# DasAltimeter_V0_3.net
KiCad netlist of a schematic drawn in EAGLE
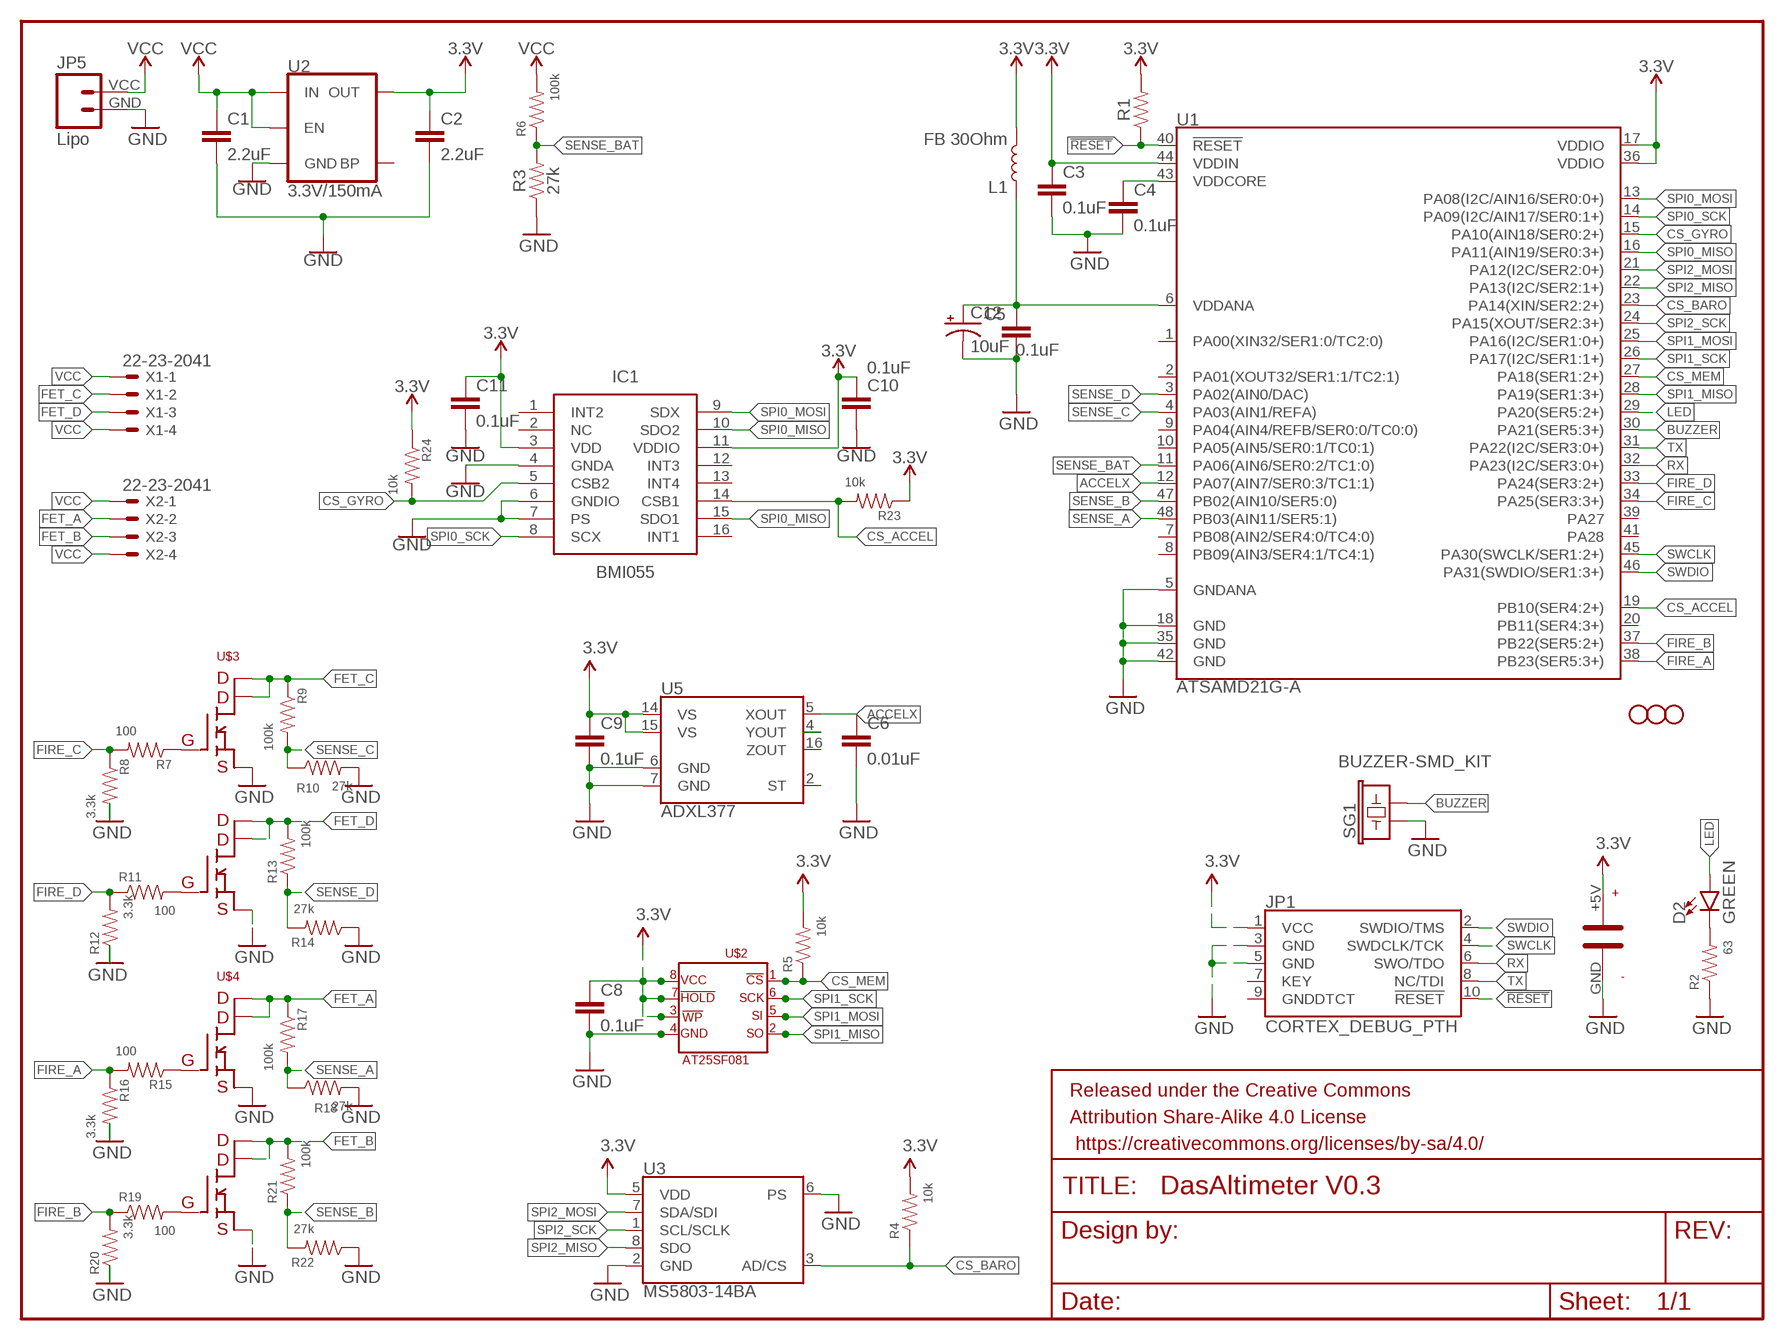
[diagram p0: schematic, sheet 1]

(export (version "E")
  (design (tool "Eeschema 10.0.6"))
  (components
    (comp (ref "C1")
      (value "2.2uF")
      (footprint "eagle-import:0603")
      (libsource (lib "eagle-import") (part "2.2UF-0603-10V-20%"))
    )
    (comp (ref "C2")
      (value "2.2uF")
      (footprint "eagle-import:0603")
      (libsource (lib "eagle-import") (part "2.2UF-0603-10V-20%"))
    )
    (comp (ref "C3")
      (value "0.1uF")
      (footprint "eagle-import:0402")
      (libsource (lib "eagle-import") (part "0.1UF-0402-16V-10%"))
    )
    (comp (ref "C4")
      (value "0.1uF")
      (footprint "eagle-import:0402")
      (libsource (lib "eagle-import") (part "0.1UF-0402-16V-10%"))
    )
    (comp (ref "C5")
      (value "0.1uF")
      (footprint "eagle-import:0402")
      (libsource (lib "eagle-import") (part "0.1UF-0402-16V-10%"))
    )
    (comp (ref "C6")
      (value "0.01uF")
      (footprint "eagle-import:0402")
      (libsource (lib "eagle-import") (part "0.1UF-0402-16V-10%"))
    )
    (comp (ref "C8")
      (value "0.1uF")
      (footprint "eagle-import:0402")
      (libsource (lib "eagle-import") (part "0.1UF-0402-16V-10%"))
    )
    (comp (ref "C9")
      (value "0.1uF")
      (footprint "eagle-import:0402")
      (libsource (lib "eagle-import") (part "0.1UF-0402-16V-10%"))
    )
    (comp (ref "C10")
      (value "0.1uF")
      (footprint "eagle-import:0402")
      (libsource (lib "eagle-import") (part "0.1UF-0402-16V-10%"))
    )
    (comp (ref "C11")
      (value "0.1uF")
      (footprint "eagle-import:0402")
      (libsource (lib "eagle-import") (part "0.1UF-0402-16V-10%"))
    )
    (comp (ref "C12")
      (value "10uF")
      (footprint "eagle-import:0603-POLAR")
      (libsource (lib "eagle-import") (part "10UF-POLAR-0603-6.3V-20%(TANT)"))
    )
    (comp (ref "D2")
      (value "GREEN")
      (footprint "eagle-import:LED-1206")
      (libsource (lib "eagle-import") (part "LED-GREEN1206"))
    )
    (comp (ref "FRAME1")
      (value "FRAME-LETTERNO_PACKAGE")
      (footprint "eagle-import:DUMMY")
      (fields (field (name "DESIGNER") "Nobody"))
      (libsource (lib "eagle-import") (part "FRAME-LETTERNO_PACKAGE"))
    )
    (comp (ref "H1")
      (value "STAND-OFFTIGHT")
      (footprint "eagle-import:STAND-OFF-TIGHT")
      (libsource (lib "eagle-import") (part "STAND-OFFTIGHT"))
    )
    (comp (ref "H2")
      (value "STAND-OFFTIGHT")
      (footprint "eagle-import:STAND-OFF-TIGHT")
      (libsource (lib "eagle-import") (part "STAND-OFFTIGHT"))
    )
    (comp (ref "H3")
      (value "STAND-OFFTIGHT")
      (footprint "eagle-import:STAND-OFF-TIGHT")
      (libsource (lib "eagle-import") (part "STAND-OFFTIGHT"))
    )
    (comp (ref "IC1")
      (value "BMI055")
      (footprint "eagle-import:BMI055")
      (libsource (lib "eagle-import") (part "BMI055"))
    )
    (comp (ref "JP1")
      (value "CORTEX_DEBUG_PTH")
      (footprint "eagle-import:2X5-PTH-1.27MM")
      (libsource (lib "eagle-import") (part "CORTEX_DEBUG_PTH"))
    )
    (comp (ref "JP5")
      (value "Lipo")
      (footprint "eagle-import:JST-2-SMD-VERT")
      (libsource (lib "eagle-import") (part "M024UCON-15767"))
    )
    (comp (ref "L1")
      (value "FB 30Ohm")
      (footprint "eagle-import:0603")
      (libsource (lib "eagle-import") (part "INDUCTOR-0603-33NH"))
    )
    (comp (ref "R1")
      (value "RESISTOR0402")
      (footprint "eagle-import:0402")
      (libsource (lib "eagle-import") (part "RESISTOR0402"))
    )
    (comp (ref "R2")
      (value "63")
      (footprint "eagle-import:0402")
      (libsource (lib "eagle-import") (part "RESISTOR0402"))
    )
    (comp (ref "R3")
      (value "27k")
      (footprint "eagle-import:0402")
      (libsource (lib "eagle-import") (part "RESISTOR0402"))
    )
    (comp (ref "R4")
      (value "10k")
      (footprint "eagle-import:0402")
      (libsource (lib "eagle-import") (part "RESISTOR0402"))
    )
    (comp (ref "R5")
      (value "10k")
      (footprint "eagle-import:0402")
      (libsource (lib "eagle-import") (part "RESISTOR0402"))
    )
    (comp (ref "R6")
      (value "100k")
      (footprint "eagle-import:0402")
      (libsource (lib "eagle-import") (part "RESISTOR0402"))
    )
    (comp (ref "R7")
      (value "100")
      (footprint "eagle-import:0402")
      (libsource (lib "eagle-import") (part "RESISTOR0402"))
    )
    (comp (ref "R8")
      (value "3.3k")
      (footprint "eagle-import:0402")
      (libsource (lib "eagle-import") (part "RESISTOR0402"))
    )
    (comp (ref "R9")
      (value "100k")
      (footprint "eagle-import:0402")
      (libsource (lib "eagle-import") (part "RESISTOR0402"))
    )
    (comp (ref "R10")
      (value "27k")
      (footprint "eagle-import:0402")
      (libsource (lib "eagle-import") (part "RESISTOR0402"))
    )
    (comp (ref "R11")
      (value "100")
      (footprint "eagle-import:0402")
      (libsource (lib "eagle-import") (part "RESISTOR0402"))
    )
    (comp (ref "R12")
      (value "3.3k")
      (footprint "eagle-import:0402")
      (libsource (lib "eagle-import") (part "RESISTOR0402"))
    )
    (comp (ref "R13")
      (value "100k")
      (footprint "eagle-import:0402")
      (libsource (lib "eagle-import") (part "RESISTOR0402"))
    )
    (comp (ref "R14")
      (value "27k")
      (footprint "eagle-import:0402")
      (libsource (lib "eagle-import") (part "RESISTOR0402"))
    )
    (comp (ref "R15")
      (value "100")
      (footprint "eagle-import:0402")
      (libsource (lib "eagle-import") (part "RESISTOR0402"))
    )
    (comp (ref "R16")
      (value "3.3k")
      (footprint "eagle-import:0402")
      (libsource (lib "eagle-import") (part "RESISTOR0402"))
    )
    (comp (ref "R17")
      (value "100k")
      (footprint "eagle-import:0402")
      (libsource (lib "eagle-import") (part "RESISTOR0402"))
    )
    (comp (ref "R18")
      (value "27k")
      (footprint "eagle-import:0402")
      (libsource (lib "eagle-import") (part "RESISTOR0402"))
    )
    (comp (ref "R19")
      (value "100")
      (footprint "eagle-import:0402")
      (libsource (lib "eagle-import") (part "RESISTOR0402"))
    )
    (comp (ref "R20")
      (value "3.3k")
      (footprint "eagle-import:0402")
      (libsource (lib "eagle-import") (part "RESISTOR0402"))
    )
    (comp (ref "R21")
      (value "100k")
      (footprint "eagle-import:0402")
      (libsource (lib "eagle-import") (part "RESISTOR0402"))
    )
    (comp (ref "R22")
      (value "27k")
      (footprint "eagle-import:0402")
      (libsource (lib "eagle-import") (part "RESISTOR0402"))
    )
    (comp (ref "R23")
      (value "10k")
      (footprint "eagle-import:0402")
      (libsource (lib "eagle-import") (part "RESISTOR0402"))
    )
    (comp (ref "R24")
      (value "10k")
      (footprint "eagle-import:0402")
      (libsource (lib "eagle-import") (part "RESISTOR0402"))
    )
    (comp (ref "SG1")
      (value "BUZZER-SMD_KIT")
      (footprint "eagle-import:BUZZER-CCV-KIT")
      (libsource (lib "eagle-import") (part "BUZZER-SMD_KIT"))
    )
    (comp (ref "U$1")
      (value "PB-5R0H104-R")
      (footprint "eagle-import:PB-5R0H104-R")
      (libsource (lib "eagle-import") (part "PB-5R0H104-R"))
    )
    (comp (ref "U$2")
      (value "AT25SF081")
      (footprint "eagle-import:AT25SF081")
      (libsource (lib "eagle-import") (part "AT25SF081"))
    )
    (comp (ref "U$3")
      (value "SI7232DN")
      (footprint "eagle-import:SI7232DN")
      (libsource (lib "eagle-import") (part "SI7232DN"))
    )
    (comp (ref "U$4")
      (value "SI7232DN")
      (footprint "eagle-import:SI7232DN")
      (libsource (lib "eagle-import") (part "SI7232DN"))
    )
    (comp (ref "U1")
      (value "ATSAMD21G-A")
      (footprint "eagle-import:TQFP-48")
      (libsource (lib "eagle-import") (part "ATSAMD21G-A"))
    )
    (comp (ref "U2")
      (value "3.3V/150mA")
      (footprint "eagle-import:SOT23-5")
      (libsource (lib "eagle-import") (part "V_REG_MIC52053.3V"))
    )
    (comp (ref "U3")
      (value "MS5803-14BA")
      (footprint "eagle-import:MS5803")
      (libsource (lib "eagle-import") (part "MS5803-14BA"))
    )
    (comp (ref "U5")
      (value "ADXL377")
      (footprint "eagle-import:LFCSP-16-3X3")
      (libsource (lib "eagle-import") (part "ADXL377"))
    )
    (comp (ref "X1")
      (value "22-23-2041")
      (footprint "eagle-import:22-23-2041")
      (fields (field (name "MF") "MOLEX"))
      (libsource (lib "eagle-import") (part "22-23-2041"))
    )
    (comp (ref "X2")
      (value "22-23-2041")
      (footprint "eagle-import:22-23-2041")
      (fields (field (name "MF") "MOLEX"))
      (libsource (lib "eagle-import") (part "22-23-2041"))
    )
  )
  (nets
    (net (code "1") (name "/~{RESET}") (class "Default")
      (node (ref "JP1") (pin "10") (pinfunction "~{RESET}_10") (pintype "bidirectional"))
      (node (ref "R1") (pin "1") (pinfunction "1_1") (pintype "passive"))
      (node (ref "U1") (pin "40") (pinfunction "~{RESET}_40") (pintype "bidirectional"))
    )
    (net (code "2") (name "3.3V") (class "Default")
      (node (ref "C10") (pin "1") (pinfunction "1_1") (pintype "passive"))
      (node (ref "C11") (pin "1") (pinfunction "1_1") (pintype "passive"))
      (node (ref "C2") (pin "1") (pinfunction "1_1") (pintype "passive"))
      (node (ref "C3") (pin "1") (pinfunction "1_1") (pintype "passive"))
      (node (ref "C8") (pin "1") (pinfunction "1_1") (pintype "passive"))
      (node (ref "C9") (pin "1") (pinfunction "1_1") (pintype "passive"))
      (node (ref "IC1") (pin "11") (pinfunction "VDDIO_11") (pintype "passive"))
      (node (ref "IC1") (pin "3") (pinfunction "VDD_3") (pintype "passive"))
      (node (ref "JP1") (pin "1") (pinfunction "VCC_1") (pintype "bidirectional"))
      (node (ref "L1") (pin "2") (pinfunction "2_2") (pintype "passive"))
      (node (ref "R1") (pin "2") (pinfunction "2_2") (pintype "passive"))
      (node (ref "R23") (pin "1") (pinfunction "1_1") (pintype "passive"))
      (node (ref "R24") (pin "1") (pinfunction "1_1") (pintype "passive"))
      (node (ref "R4") (pin "2") (pinfunction "2_2") (pintype "passive"))
      (node (ref "R5") (pin "2") (pinfunction "2_2") (pintype "passive"))
      (node (ref "U$1") (pin "+5V") (pinfunction "+5V_+5V") (pintype "bidirectional"))
      (node (ref "U$2") (pin "!HOLD") (pinfunction "~{HOLD}_!HOLD") (pintype "bidirectional"))
      (node (ref "U$2") (pin "!WP") (pinfunction "~{WP}_!WP") (pintype "bidirectional"))
      (node (ref "U$2") (pin "VCC") (pinfunction "VCC_VCC") (pintype "bidirectional"))
      (node (ref "U1") (pin "17") (pinfunction "VDDIO_17") (pintype "bidirectional"))
      (node (ref "U1") (pin "36") (pinfunction "VDDIO_36") (pintype "bidirectional"))
      (node (ref "U1") (pin "44") (pinfunction "VDDIN_44") (pintype "bidirectional"))
      (node (ref "U2") (pin "5") (pinfunction "OUT_5") (pintype "passive"))
      (node (ref "U3") (pin "5") (pinfunction "VDD_5") (pintype "bidirectional"))
      (node (ref "U5") (pin "14") (pinfunction "VS_14") (pintype "bidirectional"))
      (node (ref "U5") (pin "15") (pinfunction "VS_15") (pintype "bidirectional"))
    )
    (net (code "3") (name "ACCELX") (class "Default")
      (node (ref "C6") (pin "1") (pinfunction "1_1") (pintype "passive"))
      (node (ref "U1") (pin "12") (pinfunction "PA07(AIN7/SER0:3/TC1:1)_12") (pintype "bidirectional"))
      (node (ref "U5") (pin "5") (pinfunction "XOUT_5") (pintype "bidirectional"))
    )
    (net (code "4") (name "BUZZER") (class "Default")
      (node (ref "SG1") (pin "-") (pinfunction "2_-") (pintype "passive"))
      (node (ref "U1") (pin "30") (pinfunction "PA21(SER5:3+)_30") (pintype "bidirectional"))
    )
    (net (code "5") (name "CS_ACCEL") (class "Default")
      (node (ref "IC1") (pin "14") (pinfunction "CSB1_14") (pintype "passive"))
      (node (ref "R23") (pin "2") (pinfunction "2_2") (pintype "passive"))
      (node (ref "U1") (pin "19") (pinfunction "PB10(SER4:2+)_19") (pintype "bidirectional"))
    )
    (net (code "6") (name "CS_BARO") (class "Default")
      (node (ref "R4") (pin "1") (pinfunction "1_1") (pintype "passive"))
      (node (ref "U1") (pin "23") (pinfunction "PA14(XIN/SER2:2+)_23") (pintype "bidirectional"))
      (node (ref "U3") (pin "3") (pinfunction "AD/CS_3") (pintype "bidirectional"))
    )
    (net (code "7") (name "CS_GYRO") (class "Default")
      (node (ref "IC1") (pin "5") (pinfunction "CSB2_5") (pintype "passive"))
      (node (ref "R24") (pin "2") (pinfunction "2_2") (pintype "passive"))
      (node (ref "U1") (pin "15") (pinfunction "PA10(AIN18/SER0:2+)_15") (pintype "bidirectional"))
    )
    (net (code "8") (name "CS_MEM") (class "Default")
      (node (ref "R5") (pin "1") (pinfunction "1_1") (pintype "passive"))
      (node (ref "U$2") (pin "!CS") (pinfunction "~{CS}_!CS") (pintype "bidirectional"))
      (node (ref "U1") (pin "27") (pinfunction "PA18(SER1:2+)_27") (pintype "bidirectional"))
    )
    (net (code "9") (name "FET_A") (class "Default")
      (node (ref "R17") (pin "1") (pinfunction "1_1") (pintype "passive"))
      (node (ref "U$4") (pin "7") (pinfunction "PIN7_7") (pintype "bidirectional"))
      (node (ref "U$4") (pin "8") (pinfunction "PIN8_8") (pintype "bidirectional"))
      (node (ref "U$4") (pin "9") (pinfunction "PIN8_9") (pintype "bidirectional"))
      (node (ref "X2") (pin "2") (pinfunction "S_2") (pintype "passive"))
    )
    (net (code "10") (name "FET_B") (class "Default")
      (node (ref "R21") (pin "2") (pinfunction "2_2") (pintype "passive"))
      (node (ref "U$4") (pin "10") (pinfunction "PIN5_10") (pintype "bidirectional"))
      (node (ref "U$4") (pin "5") (pinfunction "PIN5_5") (pintype "bidirectional"))
      (node (ref "U$4") (pin "6") (pinfunction "PIN6_6") (pintype "bidirectional"))
      (node (ref "X2") (pin "3") (pinfunction "S_3") (pintype "passive"))
    )
    (net (code "11") (name "FET_C") (class "Default")
      (node (ref "R9") (pin "1") (pinfunction "1_1") (pintype "passive"))
      (node (ref "U$3") (pin "7") (pinfunction "PIN7_7") (pintype "bidirectional"))
      (node (ref "U$3") (pin "8") (pinfunction "PIN8_8") (pintype "bidirectional"))
      (node (ref "U$3") (pin "9") (pinfunction "PIN8_9") (pintype "bidirectional"))
      (node (ref "X1") (pin "2") (pinfunction "S_2") (pintype "passive"))
    )
    (net (code "12") (name "FET_D") (class "Default")
      (node (ref "R13") (pin "2") (pinfunction "2_2") (pintype "passive"))
      (node (ref "U$3") (pin "10") (pinfunction "PIN5_10") (pintype "bidirectional"))
      (node (ref "U$3") (pin "5") (pinfunction "PIN5_5") (pintype "bidirectional"))
      (node (ref "U$3") (pin "6") (pinfunction "PIN6_6") (pintype "bidirectional"))
      (node (ref "X1") (pin "3") (pinfunction "S_3") (pintype "passive"))
    )
    (net (code "13") (name "FIRE_A") (class "Default")
      (node (ref "R15") (pin "2") (pinfunction "2_2") (pintype "passive"))
      (node (ref "R16") (pin "1") (pinfunction "1_1") (pintype "passive"))
      (node (ref "U1") (pin "38") (pinfunction "PB23(SER5:3+)_38") (pintype "bidirectional"))
    )
    (net (code "14") (name "FIRE_B") (class "Default")
      (node (ref "R19") (pin "1") (pinfunction "1_1") (pintype "passive"))
      (node (ref "R20") (pin "2") (pinfunction "2_2") (pintype "passive"))
      (node (ref "U1") (pin "37") (pinfunction "PB22(SER5:2+)_37") (pintype "bidirectional"))
    )
    (net (code "15") (name "FIRE_C") (class "Default")
      (node (ref "R7") (pin "2") (pinfunction "2_2") (pintype "passive"))
      (node (ref "R8") (pin "1") (pinfunction "1_1") (pintype "passive"))
      (node (ref "U1") (pin "34") (pinfunction "PA25(SER3:3+)_34") (pintype "bidirectional"))
    )
    (net (code "16") (name "FIRE_D") (class "Default")
      (node (ref "R11") (pin "1") (pinfunction "1_1") (pintype "passive"))
      (node (ref "R12") (pin "2") (pinfunction "2_2") (pintype "passive"))
      (node (ref "U1") (pin "33") (pinfunction "PA24(SER3:2+)_33") (pintype "bidirectional"))
    )
    (net (code "17") (name "GND") (class "Default")
      (node (ref "C1") (pin "2") (pinfunction "2_2") (pintype "passive"))
      (node (ref "C10") (pin "2") (pinfunction "2_2") (pintype "passive"))
      (node (ref "C11") (pin "2") (pinfunction "2_2") (pintype "passive"))
      (node (ref "C12") (pin "-") (pinfunction "-_-") (pintype "passive"))
      (node (ref "C2") (pin "2") (pinfunction "2_2") (pintype "passive"))
      (node (ref "C3") (pin "2") (pinfunction "2_2") (pintype "passive"))
      (node (ref "C4") (pin "2") (pinfunction "2_2") (pintype "passive"))
      (node (ref "C5") (pin "2") (pinfunction "2_2") (pintype "passive"))
      (node (ref "C6") (pin "2") (pinfunction "2_2") (pintype "passive"))
      (node (ref "C8") (pin "2") (pinfunction "2_2") (pintype "passive"))
      (node (ref "C9") (pin "2") (pinfunction "2_2") (pintype "passive"))
      (node (ref "IC1") (pin "4") (pinfunction "GNDA_4") (pintype "passive"))
      (node (ref "IC1") (pin "6") (pinfunction "GNDIO_6") (pintype "passive"))
      (node (ref "IC1") (pin "7") (pinfunction "PS_7") (pintype "passive"))
      (node (ref "JP1") (pin "3") (pinfunction "GND_3") (pintype "bidirectional"))
      (node (ref "JP1") (pin "5") (pinfunction "GND_5") (pintype "bidirectional"))
      (node (ref "JP5") (pin "GND") (pinfunction "1_GND") (pintype "passive"))
      (node (ref "R10") (pin "2") (pinfunction "2_2") (pintype "passive"))
      (node (ref "R12") (pin "1") (pinfunction "1_1") (pintype "passive"))
      (node (ref "R14") (pin "1") (pinfunction "1_1") (pintype "passive"))
      (node (ref "R16") (pin "2") (pinfunction "2_2") (pintype "passive"))
      (node (ref "R18") (pin "2") (pinfunction "2_2") (pintype "passive"))
      (node (ref "R2") (pin "1") (pinfunction "1_1") (pintype "passive"))
      (node (ref "R20") (pin "1") (pinfunction "1_1") (pintype "passive"))
      (node (ref "R22") (pin "1") (pinfunction "1_1") (pintype "passive"))
      (node (ref "R3") (pin "1") (pinfunction "1_1") (pintype "passive"))
      (node (ref "R8") (pin "2") (pinfunction "2_2") (pintype "passive"))
      (node (ref "SG1") (pin "+") (pinfunction "1_+") (pintype "passive"))
      (node (ref "U$1") (pin "GND") (pinfunction "GND_GND") (pintype "bidirectional"))
      (node (ref "U$2") (pin "GND") (pinfunction "GND_GND") (pintype "bidirectional"))
      (node (ref "U$3") (pin "1") (pinfunction "PIN1_1") (pintype "bidirectional"))
      (node (ref "U$3") (pin "3") (pinfunction "PIN3_3") (pintype "bidirectional"))
      (node (ref "U$4") (pin "1") (pinfunction "PIN1_1") (pintype "bidirectional"))
      (node (ref "U$4") (pin "3") (pinfunction "PIN3_3") (pintype "bidirectional"))
      (node (ref "U1") (pin "18") (pinfunction "GND_18") (pintype "bidirectional"))
      (node (ref "U1") (pin "35") (pinfunction "GND_35") (pintype "bidirectional"))
      (node (ref "U1") (pin "42") (pinfunction "GND_42") (pintype "bidirectional"))
      (node (ref "U1") (pin "5") (pinfunction "GNDANA_5") (pintype "bidirectional"))
      (node (ref "U2") (pin "2") (pinfunction "GND_2") (pintype "input"))
      (node (ref "U3") (pin "2") (pinfunction "GND_2") (pintype "bidirectional"))
      (node (ref "U3") (pin "6") (pinfunction "PS_6") (pintype "bidirectional"))
      (node (ref "U5") (pin "6") (pinfunction "GND_6") (pintype "bidirectional"))
      (node (ref "U5") (pin "7") (pinfunction "GND_7") (pintype "bidirectional"))
    )
    (net (code "18") (name "LED") (class "Default")
      (node (ref "D2") (pin "A") (pinfunction "A_A") (pintype "passive"))
      (node (ref "U1") (pin "29") (pinfunction "PA20(SER5:2+)_29") (pintype "bidirectional"))
    )
    (net (code "19") (name "Net-(D2-PadC)") (class "Default")
      (node (ref "D2") (pin "C") (pinfunction "C_C") (pintype "passive"))
      (node (ref "R2") (pin "2") (pinfunction "2_2") (pintype "passive"))
    )
    (net (code "20") (name "Net-(U$3-PIN2)") (class "Default")
      (node (ref "R7") (pin "1") (pinfunction "1_1") (pintype "passive"))
      (node (ref "U$3") (pin "2") (pinfunction "PIN2_2") (pintype "bidirectional"))
    )
    (net (code "21") (name "Net-(U$3-PIN4)") (class "Default")
      (node (ref "R11") (pin "2") (pinfunction "2_2") (pintype "passive"))
      (node (ref "U$3") (pin "4") (pinfunction "PIN4_4") (pintype "bidirectional"))
    )
    (net (code "22") (name "Net-(U$4-PIN2)") (class "Default")
      (node (ref "R15") (pin "1") (pinfunction "1_1") (pintype "passive"))
      (node (ref "U$4") (pin "2") (pinfunction "PIN2_2") (pintype "bidirectional"))
    )
    (net (code "23") (name "Net-(U$4-PIN4)") (class "Default")
      (node (ref "R19") (pin "2") (pinfunction "2_2") (pintype "passive"))
      (node (ref "U$4") (pin "4") (pinfunction "PIN4_4") (pintype "bidirectional"))
    )
    (net (code "24") (name "Net-(U1-VDDANA)") (class "Default")
      (node (ref "C12") (pin "+") (pinfunction "+_+") (pintype "passive"))
      (node (ref "C5") (pin "1") (pinfunction "1_1") (pintype "passive"))
      (node (ref "L1") (pin "1") (pinfunction "1_1") (pintype "passive"))
      (node (ref "U1") (pin "6") (pinfunction "VDDANA_6") (pintype "bidirectional"))
    )
    (net (code "25") (name "Net-(U1-VDDCORE)") (class "Default")
      (node (ref "C4") (pin "1") (pinfunction "1_1") (pintype "passive"))
      (node (ref "U1") (pin "43") (pinfunction "VDDCORE_43") (pintype "bidirectional"))
    )
    (net (code "26") (name "RX") (class "Default")
      (node (ref "JP1") (pin "6") (pinfunction "SWO/TDO_6") (pintype "bidirectional"))
      (node (ref "U1") (pin "32") (pinfunction "PA23(I2C/SER3:0+)_32") (pintype "bidirectional"))
    )
    (net (code "27") (name "SENSE_A") (class "Default")
      (node (ref "R17") (pin "2") (pinfunction "2_2") (pintype "passive"))
      (node (ref "R18") (pin "1") (pinfunction "1_1") (pintype "passive"))
      (node (ref "U1") (pin "48") (pinfunction "PB03(AIN11/SER5:1)_48") (pintype "bidirectional"))
    )
    (net (code "28") (name "SENSE_B") (class "Default")
      (node (ref "R21") (pin "1") (pinfunction "1_1") (pintype "passive"))
      (node (ref "R22") (pin "2") (pinfunction "2_2") (pintype "passive"))
      (node (ref "U1") (pin "47") (pinfunction "PB02(AIN10/SER5:0)_47") (pintype "bidirectional"))
    )
    (net (code "29") (name "SENSE_BAT") (class "Default")
      (node (ref "R3") (pin "2") (pinfunction "2_2") (pintype "passive"))
      (node (ref "R6") (pin "1") (pinfunction "1_1") (pintype "passive"))
      (node (ref "U1") (pin "11") (pinfunction "PA06(AIN6/SER0:2/TC1:0)_11") (pintype "bidirectional"))
    )
    (net (code "30") (name "SENSE_C") (class "Default")
      (node (ref "R10") (pin "1") (pinfunction "1_1") (pintype "passive"))
      (node (ref "R9") (pin "2") (pinfunction "2_2") (pintype "passive"))
      (node (ref "U1") (pin "4") (pinfunction "PA03(AIN1/REFA)_4") (pintype "bidirectional"))
    )
    (net (code "31") (name "SENSE_D") (class "Default")
      (node (ref "R13") (pin "1") (pinfunction "1_1") (pintype "passive"))
      (node (ref "R14") (pin "2") (pinfunction "2_2") (pintype "passive"))
      (node (ref "U1") (pin "3") (pinfunction "PA02(AIN0/DAC)_3") (pintype "bidirectional"))
    )
    (net (code "32") (name "SPI0_MISO") (class "Default")
      (node (ref "IC1") (pin "10") (pinfunction "SDO2_10") (pintype "passive"))
      (node (ref "IC1") (pin "15") (pinfunction "SDO1_15") (pintype "passive"))
      (node (ref "U1") (pin "16") (pinfunction "PA11(AIN19/SER0:3+)_16") (pintype "bidirectional"))
    )
    (net (code "33") (name "SPI0_MOSI") (class "Default")
      (node (ref "IC1") (pin "9") (pinfunction "SDX_9") (pintype "passive"))
      (node (ref "U1") (pin "13") (pinfunction "PA08(I2C/AIN16/SER0:0+)_13") (pintype "bidirectional"))
    )
    (net (code "34") (name "SPI0_SCK") (class "Default")
      (node (ref "IC1") (pin "8") (pinfunction "SCX_8") (pintype "passive"))
      (node (ref "U1") (pin "14") (pinfunction "PA09(I2C/AIN17/SER0:1+)_14") (pintype "bidirectional"))
    )
    (net (code "35") (name "SPI1_MISO") (class "Default")
      (node (ref "U$2") (pin "SO") (pinfunction "SO_SO") (pintype "bidirectional"))
      (node (ref "U1") (pin "28") (pinfunction "PA19(SER1:3+)_28") (pintype "bidirectional"))
    )
    (net (code "36") (name "SPI1_MOSI") (class "Default")
      (node (ref "U$2") (pin "SI") (pinfunction "SI_SI") (pintype "bidirectional"))
      (node (ref "U1") (pin "25") (pinfunction "PA16(I2C/SER1:0+)_25") (pintype "bidirectional"))
    )
    (net (code "37") (name "SPI1_SCK") (class "Default")
      (node (ref "U$2") (pin "SCK") (pinfunction "SCK_SCK") (pintype "bidirectional"))
      (node (ref "U1") (pin "26") (pinfunction "PA17(I2C/SER1:1+)_26") (pintype "bidirectional"))
    )
    (net (code "38") (name "SPI2_MISO") (class "Default")
      (node (ref "U1") (pin "22") (pinfunction "PA13(I2C/SER2:1+)_22") (pintype "bidirectional"))
      (node (ref "U3") (pin "8") (pinfunction "SDO_8") (pintype "bidirectional"))
    )
    (net (code "39") (name "SPI2_MOSI") (class "Default")
      (node (ref "U1") (pin "21") (pinfunction "PA12(I2C/SER2:0+)_21") (pintype "bidirectional"))
      (node (ref "U3") (pin "7") (pinfunction "SDA/SDI_7") (pintype "bidirectional"))
    )
    (net (code "40") (name "SPI2_SCK") (class "Default")
      (node (ref "U1") (pin "24") (pinfunction "PA15(XOUT/SER2:3+)_24") (pintype "bidirectional"))
      (node (ref "U3") (pin "1") (pinfunction "SCL/SCLK_1") (pintype "bidirectional"))
    )
    (net (code "41") (name "SWCLK") (class "Default")
      (node (ref "JP1") (pin "4") (pinfunction "SWDCLK/TCK_4") (pintype "bidirectional"))
      (node (ref "U1") (pin "45") (pinfunction "PA30(SWCLK/SER1:2+)_45") (pintype "bidirectional"))
    )
    (net (code "42") (name "SWDIO") (class "Default")
      (node (ref "JP1") (pin "2") (pinfunction "SWDIO/TMS_2") (pintype "bidirectional"))
      (node (ref "U1") (pin "46") (pinfunction "PA31(SWDIO/SER1:3+)_46") (pintype "bidirectional"))
    )
    (net (code "43") (name "TX") (class "Default")
      (node (ref "JP1") (pin "8") (pinfunction "NC/TDI_8") (pintype "bidirectional"))
      (node (ref "U1") (pin "31") (pinfunction "PA22(I2C/SER3:0+)_31") (pintype "bidirectional"))
    )
    (net (code "44") (name "VCC") (class "Default")
      (node (ref "C1") (pin "1") (pinfunction "1_1") (pintype "passive"))
      (node (ref "JP5") (pin "VCC") (pinfunction "2_VCC") (pintype "passive"))
      (node (ref "R6") (pin "2") (pinfunction "2_2") (pintype "passive"))
      (node (ref "U2") (pin "1") (pinfunction "IN_1") (pintype "input"))
      (node (ref "U2") (pin "3") (pinfunction "EN_3") (pintype "input"))
      (node (ref "X1") (pin "1") (pinfunction "S_1") (pintype "passive"))
      (node (ref "X1") (pin "4") (pinfunction "S_4") (pintype "passive"))
      (node (ref "X2") (pin "1") (pinfunction "S_1") (pintype "passive"))
      (node (ref "X2") (pin "4") (pinfunction "S_4") (pintype "passive"))
    )
    (net (code "45") (name "unconnected-(IC1-INT1-Pad16)") (class "Default")
      (node (ref "IC1") (pin "16") (pinfunction "INT1_16") (pintype "passive"))
    )
    (net (code "46") (name "unconnected-(IC1-INT2-Pad1)") (class "Default")
      (node (ref "IC1") (pin "1") (pinfunction "INT2_1") (pintype "passive"))
    )
    (net (code "47") (name "unconnected-(IC1-INT3-Pad12)") (class "Default")
      (node (ref "IC1") (pin "12") (pinfunction "INT3_12") (pintype "passive"))
    )
    (net (code "48") (name "unconnected-(IC1-INT4-Pad13)") (class "Default")
      (node (ref "IC1") (pin "13") (pinfunction "INT4_13") (pintype "passive"))
    )
    (net (code "49") (name "unconnected-(IC1-NC-Pad2)") (class "Default")
      (node (ref "IC1") (pin "2") (pinfunction "NC_2") (pintype "no_connect"))
    )
    (net (code "50") (name "unconnected-(JP1-GNDDTCT-Pad9)") (class "Default")
      (node (ref "JP1") (pin "9") (pinfunction "GNDDTCT_9") (pintype "bidirectional"))
    )
    (net (code "51") (name "unconnected-(JP1-KEY-Pad7)") (class "Default")
      (node (ref "JP1") (pin "7") (pinfunction "KEY_7") (pintype "bidirectional"))
    )
    (net (code "52") (name "unconnected-(U1-PA00(XIN32{slash}SER1:0{slash}TC2:0)-Pad1)") (class "Default")
      (node (ref "U1") (pin "1") (pinfunction "PA00(XIN32/SER1:0/TC2:0)_1") (pintype "bidirectional"))
    )
    (net (code "53") (name "unconnected-(U1-PA01(XOUT32{slash}SER1:1{slash}TC2:1)-Pad2)") (class "Default")
      (node (ref "U1") (pin "2") (pinfunction "PA01(XOUT32/SER1:1/TC2:1)_2") (pintype "bidirectional"))
    )
    (net (code "54") (name "unconnected-(U1-PA04(AIN4{slash}REFB{slash}SER0:0{slash}TC0:0)-Pad9)") (class "Default")
      (node (ref "U1") (pin "9") (pinfunction "PA04(AIN4/REFB/SER0:0/TC0:0)_9") (pintype "bidirectional"))
    )
    (net (code "55") (name "unconnected-(U1-PA05(AIN5{slash}SER0:1{slash}TC0:1)-Pad10)") (class "Default")
      (node (ref "U1") (pin "10") (pinfunction "PA05(AIN5/SER0:1/TC0:1)_10") (pintype "bidirectional"))
    )
    (net (code "56") (name "unconnected-(U1-PA27-Pad39)") (class "Default")
      (node (ref "U1") (pin "39") (pinfunction "PA27_39") (pintype "bidirectional"))
    )
    (net (code "57") (name "unconnected-(U1-PA28-Pad41)") (class "Default")
      (node (ref "U1") (pin "41") (pinfunction "PA28_41") (pintype "bidirectional"))
    )
    (net (code "58") (name "unconnected-(U1-PB08(AIN2{slash}SER4:0{slash}TC4:0)-Pad7)") (class "Default")
      (node (ref "U1") (pin "7") (pinfunction "PB08(AIN2/SER4:0/TC4:0)_7") (pintype "bidirectional"))
    )
    (net (code "59") (name "unconnected-(U1-PB09(AIN3{slash}SER4:1{slash}TC4:1)-Pad8)") (class "Default")
      (node (ref "U1") (pin "8") (pinfunction "PB09(AIN3/SER4:1/TC4:1)_8") (pintype "bidirectional"))
    )
    (net (code "60") (name "unconnected-(U1-PB11(SER4:3+)-Pad20)") (class "Default")
      (node (ref "U1") (pin "20") (pinfunction "PB11(SER4:3+)_20") (pintype "bidirectional"))
    )
    (net (code "61") (name "unconnected-(U2-BP-Pad4)") (class "Default")
      (node (ref "U2") (pin "4") (pinfunction "BP_4") (pintype "input"))
    )
    (net (code "62") (name "unconnected-(U5-ST-Pad2)") (class "Default")
      (node (ref "U5") (pin "2") (pinfunction "ST_2") (pintype "bidirectional"))
    )
    (net (code "63") (name "unconnected-(U5-YOUT-Pad4)") (class "Default")
      (node (ref "U5") (pin "4") (pinfunction "YOUT_4") (pintype "bidirectional"))
    )
    (net (code "64") (name "unconnected-(U5-ZOUT-Pad16)") (class "Default")
      (node (ref "U5") (pin "16") (pinfunction "ZOUT_16") (pintype "bidirectional"))
    )
  )
)
